# Analog_Channel.net
KiCad netlist of a schematic drawn in Altium Designer
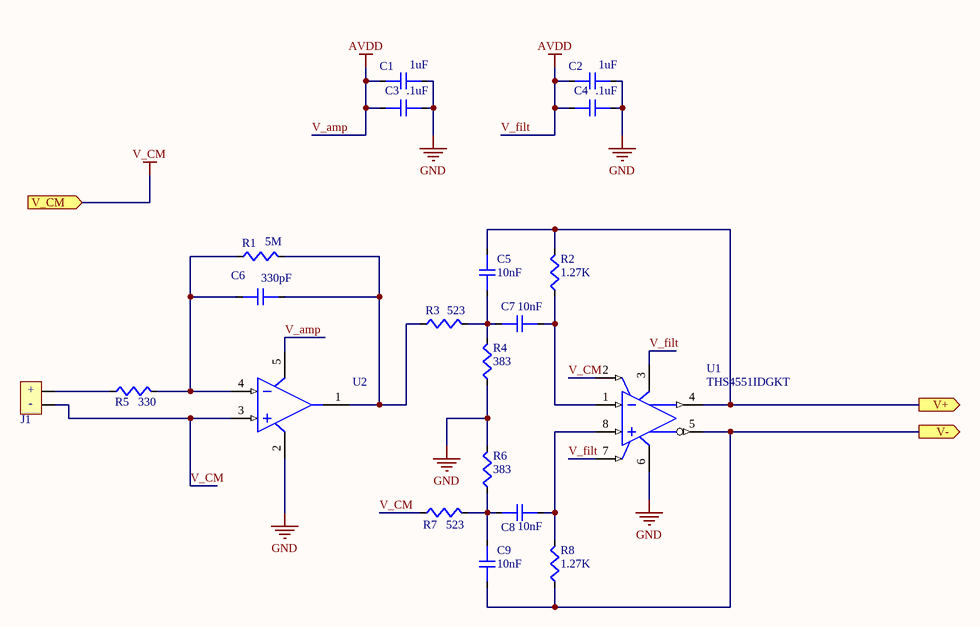
[diagram p0: Analog Channel.SchDoc]

(export (version "E")
  (design (tool "Eeschema 10.0.6"))
  (components
    (comp (ref "C1")
      (value "1uF")
      (footprint "C0603")
      (description "Cap Ceramic 1uF 16V X7R 10% SMD 0603 125C T/R")
      (fields (field (name "TOLERANCE") "10%") (field (name "VOLTAGE") "16V"))
      (libsource (lib "DAQ") (part "CL10B105KO8NNNC"))
    )
    (comp (ref "C2")
      (value "1uF")
      (footprint "C0603")
      (description "Cap Ceramic 1uF 16V X7R 10% SMD 0603 125C T/R")
      (fields (field (name "TOLERANCE") "10%") (field (name "VOLTAGE") "16V"))
      (libsource (lib "DAQ") (part "CL10B105KO8NNNC"))
    )
    (comp (ref "C3")
      (value ".1uF")
      (footprint "C0603")
      (description "0603 0.1 uF 16 V ±5 % Tolerance X7R SMT Multilayer Ceramic Chip Capacitor")
      (fields (field (name "TOLERANCE") "5%"))
      (libsource (lib "DAQ") (part "VJ0603Y104JXJCW1BC"))
    )
    (comp (ref "C4")
      (value ".1uF")
      (footprint "C0603")
      (description "0603 0.1 uF 16 V ±5 % Tolerance X7R SMT Multilayer Ceramic Chip Capacitor")
      (fields (field (name "TOLERANCE") "5%"))
      (libsource (lib "DAQ") (part "VJ0603Y104JXJCW1BC"))
    )
    (comp (ref "C5")
      (value "10nF")
      (footprint "C0603")
      (description "CAP CER 10000PF 25V C0G/NP0 0603")
      (fields (field (name "TOLERANCE") "5%"))
      (libsource (lib "DAQ") (part "C0603X103F3GACAUTO"))
    )
    (comp (ref "C6")
      (value "330pF")
      (footprint "C0603")
      (description "CAP CER 330PF 50V X7R 0603")
      (fields (field (name "TOLERANCE") "10%"))
      (libsource (lib "DAQ") (part "CC0603KRX7R9BB331"))
    )
    (comp (ref "C7")
      (value "10nF")
      (footprint "C0603")
      (description "CAP CER 10000PF 25V C0G/NP0 0603")
      (fields (field (name "TOLERANCE") "5%"))
      (libsource (lib "DAQ") (part "C0603X103F3GACAUTO"))
    )
    (comp (ref "C8")
      (value "10nF")
      (footprint "C0603")
      (description "CAP CER 10000PF 25V C0G/NP0 0603")
      (fields (field (name "TOLERANCE") "5%"))
      (libsource (lib "DAQ") (part "C0603X103F3GACAUTO"))
    )
    (comp (ref "C9")
      (value "10nF")
      (footprint "C0603")
      (description "CAP CER 10000PF 25V C0G/NP0 0603")
      (fields (field (name "TOLERANCE") "5%"))
      (libsource (lib "DAQ") (part "C0603X103F3GACAUTO"))
    )
    (comp (ref "J1")
      (value "J")
      (footprint "EPC.00.250.NTN")
      (libsource (lib "DAQ") (part "hydrophone_connector"))
    )
    (comp (ref "R1")
      (value "5M")
      (footprint "R0603")
      (description "RES SMD 5M OHM 1% 1/10W 0603")
      (fields (field (name "TOLERANCE") "1%"))
      (libsource (lib "DAQ") (part "HVC0603T5004FET"))
    )
    (comp (ref "R2")
      (value "1.27K")
      (footprint "R0603")
      (description "RES SMD 1.27K OHM 0.1% 1/6W 0603")
      (fields (field (name "TOLERANCE") "1%"))
      (libsource (lib "DAQ") (part "2-2176088-2"))
    )
    (comp (ref "R3")
      (value "523")
      (footprint "R0603")
      (description "RES SMD 523 OHM 0.1% 1/6W 0603")
      (fields (field (name "TOLERANCE") "1%"))
      (libsource (lib "DAQ") (part "RP73PF1J523RBTDF"))
    )
    (comp (ref "R4")
      (value "383")
      (footprint "R0603")
      (description "RES SMD 383 OHM ±0.1% 0.167W, 1/6W Chip Resistor 0603 (1608 Metric) - Thin Film")
      (fields (field (name "TOLERANCE") "1%"))
      (libsource (lib "DAQ") (part "RP73PF1J383RBTDF"))
    )
    (comp (ref "R5")
      (value "330")
      (footprint "R0603")
      (description "RES SMD 330 OHM 1% 1/8W 0603")
      (fields (field (name "TOLERANCE") "1%"))
      (libsource (lib "DAQ") (part "MCT06030C3300FP500"))
    )
    (comp (ref "R6")
      (value "383")
      (footprint "R0603")
      (description "RES SMD 383 OHM ±0.1% 0.167W, 1/6W Chip Resistor 0603 (1608 Metric) - Thin Film")
      (fields (field (name "TOLERANCE") "1%"))
      (libsource (lib "DAQ") (part "RP73PF1J383RBTDF"))
    )
    (comp (ref "R7")
      (value "523")
      (footprint "R0603")
      (description "RES SMD 523 OHM 0.1% 1/6W 0603")
      (fields (field (name "TOLERANCE") "1%"))
      (libsource (lib "DAQ") (part "RP73PF1J523RBTDF"))
    )
    (comp (ref "R8")
      (value "1.27K")
      (footprint "R0603")
      (description "RES SMD 1.27K OHM 0.1% 1/6W 0603")
      (fields (field (name "TOLERANCE") "1%"))
      (libsource (lib "DAQ") (part "2-2176088-2"))
    )
    (comp (ref "U1")
      (value "THS4551IDGKT")
      (footprint "8-VSSOP-THS4551")
      (description "Low Noise, Precision, 150MHz, Fully Differential Amplifier 8-VSSOP -40 to 125")
      (libsource (lib "DAQ") (part "THS4551IDGKT"))
    )
    (comp (ref "U2")
      (value "OPA320")
      (footprint "SOT-23-5")
      (description "General Purpose Amplifier Circuit Rail-to-Rail SOT-23-5")
      (libsource (lib "DAQ") (part "OPA320AQDBVRQ1"))
    )
  )
  (nets
    (net (code "1") (name "/V+") (class "Default")
      (node (ref "C5") (pin "2") (pinfunction "2_2") (pintype "passive"))
      (node (ref "R2") (pin "2") (pinfunction "2_2") (pintype "passive"))
      (node (ref "U1") (pin "4") (pinfunction "VOUT+_4") (pintype "output"))
    )
    (net (code "2") (name "/V-") (class "Default")
      (node (ref "C9") (pin "1") (pinfunction "1_1") (pintype "passive"))
      (node (ref "R8") (pin "1") (pinfunction "1_1") (pintype "passive"))
      (node (ref "U1") (pin "5") (pinfunction "VOUT-_5") (pintype "output"))
    )
    (net (code "3") (name "AVDD") (class "Default")
      (node (ref "C1") (pin "2") (pinfunction "2_2") (pintype "passive"))
      (node (ref "C2") (pin "2") (pinfunction "2_2") (pintype "passive"))
      (node (ref "C3") (pin "1") (pinfunction "1_1") (pintype "passive"))
      (node (ref "C4") (pin "1") (pinfunction "1_1") (pintype "passive"))
      (node (ref "U1") (pin "3") (pinfunction "VS+_3") (pintype "power_in"))
      (node (ref "U1") (pin "7") (pinfunction "~{PD}_7") (pintype "input"))
      (node (ref "U2") (pin "5") (pinfunction "VS+_5") (pintype "power_in"))
    )
    (net (code "4") (name "GND") (class "Default")
      (node (ref "C1") (pin "1") (pinfunction "1_1") (pintype "passive"))
      (node (ref "C2") (pin "1") (pinfunction "1_1") (pintype "passive"))
      (node (ref "C3") (pin "2") (pinfunction "2_2") (pintype "passive"))
      (node (ref "C4") (pin "2") (pinfunction "2_2") (pintype "passive"))
      (node (ref "R4") (pin "1") (pinfunction "1_1") (pintype "passive"))
      (node (ref "R6") (pin "2") (pinfunction "2_2") (pintype "passive"))
      (node (ref "U1") (pin "6") (pinfunction "VS-_6") (pintype "power_in"))
      (node (ref "U2") (pin "2") (pinfunction "VS-_2") (pintype "power_in"))
    )
    (net (code "5") (name "Net-(C5-Pad1)") (class "Default")
      (node (ref "C5") (pin "1") (pinfunction "1_1") (pintype "passive"))
      (node (ref "C7") (pin "1") (pinfunction "1_1") (pintype "passive"))
      (node (ref "R3") (pin "2") (pinfunction "2_2") (pintype "passive"))
      (node (ref "R4") (pin "2") (pinfunction "2_2") (pintype "passive"))
    )
    (net (code "6") (name "Net-(C8-Pad1)") (class "Default")
      (node (ref "C8") (pin "1") (pinfunction "1_1") (pintype "passive"))
      (node (ref "C9") (pin "2") (pinfunction "2_2") (pintype "passive"))
      (node (ref "R6") (pin "1") (pinfunction "1_1") (pintype "passive"))
      (node (ref "R7") (pin "2") (pinfunction "2_2") (pintype "passive"))
    )
    (net (code "7") (name "Net-(J1-Pad1)") (class "Default")
      (node (ref "J1") (pin "1") (pinfunction "1_1") (pintype "passive"))
      (node (ref "R5") (pin "1") (pinfunction "1_1") (pintype "passive"))
    )
    (net (code "8") (name "Net-(U1-VIN+)") (class "Default")
      (node (ref "C8") (pin "2") (pinfunction "2_2") (pintype "passive"))
      (node (ref "R8") (pin "2") (pinfunction "2_2") (pintype "passive"))
      (node (ref "U1") (pin "8") (pinfunction "VIN+_8") (pintype "input"))
    )
    (net (code "9") (name "Net-(U1-VIN-)") (class "Default")
      (node (ref "C7") (pin "2") (pinfunction "2_2") (pintype "passive"))
      (node (ref "R2") (pin "1") (pinfunction "1_1") (pintype "passive"))
      (node (ref "U1") (pin "1") (pinfunction "VIN-_1") (pintype "input"))
    )
    (net (code "10") (name "Net-(U2--IN)") (class "Default")
      (node (ref "C6") (pin "1") (pinfunction "1_1") (pintype "passive"))
      (node (ref "R1") (pin "1") (pinfunction "1_1") (pintype "passive"))
      (node (ref "R5") (pin "2") (pinfunction "2_2") (pintype "passive"))
      (node (ref "U2") (pin "4") (pinfunction "-IN_4") (pintype "input"))
    )
    (net (code "11") (name "Net-(U2-OUT)") (class "Default")
      (node (ref "C6") (pin "2") (pinfunction "2_2") (pintype "passive"))
      (node (ref "R1") (pin "2") (pinfunction "2_2") (pintype "passive"))
      (node (ref "R3") (pin "1") (pinfunction "1_1") (pintype "passive"))
      (node (ref "U2") (pin "1") (pinfunction "OUT_1") (pintype "passive"))
    )
    (net (code "12") (name "V_CM") (class "Default")
      (node (ref "J1") (pin "2") (pinfunction "2_2") (pintype "passive"))
      (node (ref "R7") (pin "1") (pinfunction "1_1") (pintype "passive"))
      (node (ref "U1") (pin "2") (pinfunction "VOCM_2") (pintype "input"))
      (node (ref "U2") (pin "3") (pinfunction "+IN_3") (pintype "input"))
    )
  )
)
